# Kasli-SOC_bank500-501.net
KiCad netlist of a schematic drawn in Altium Designer
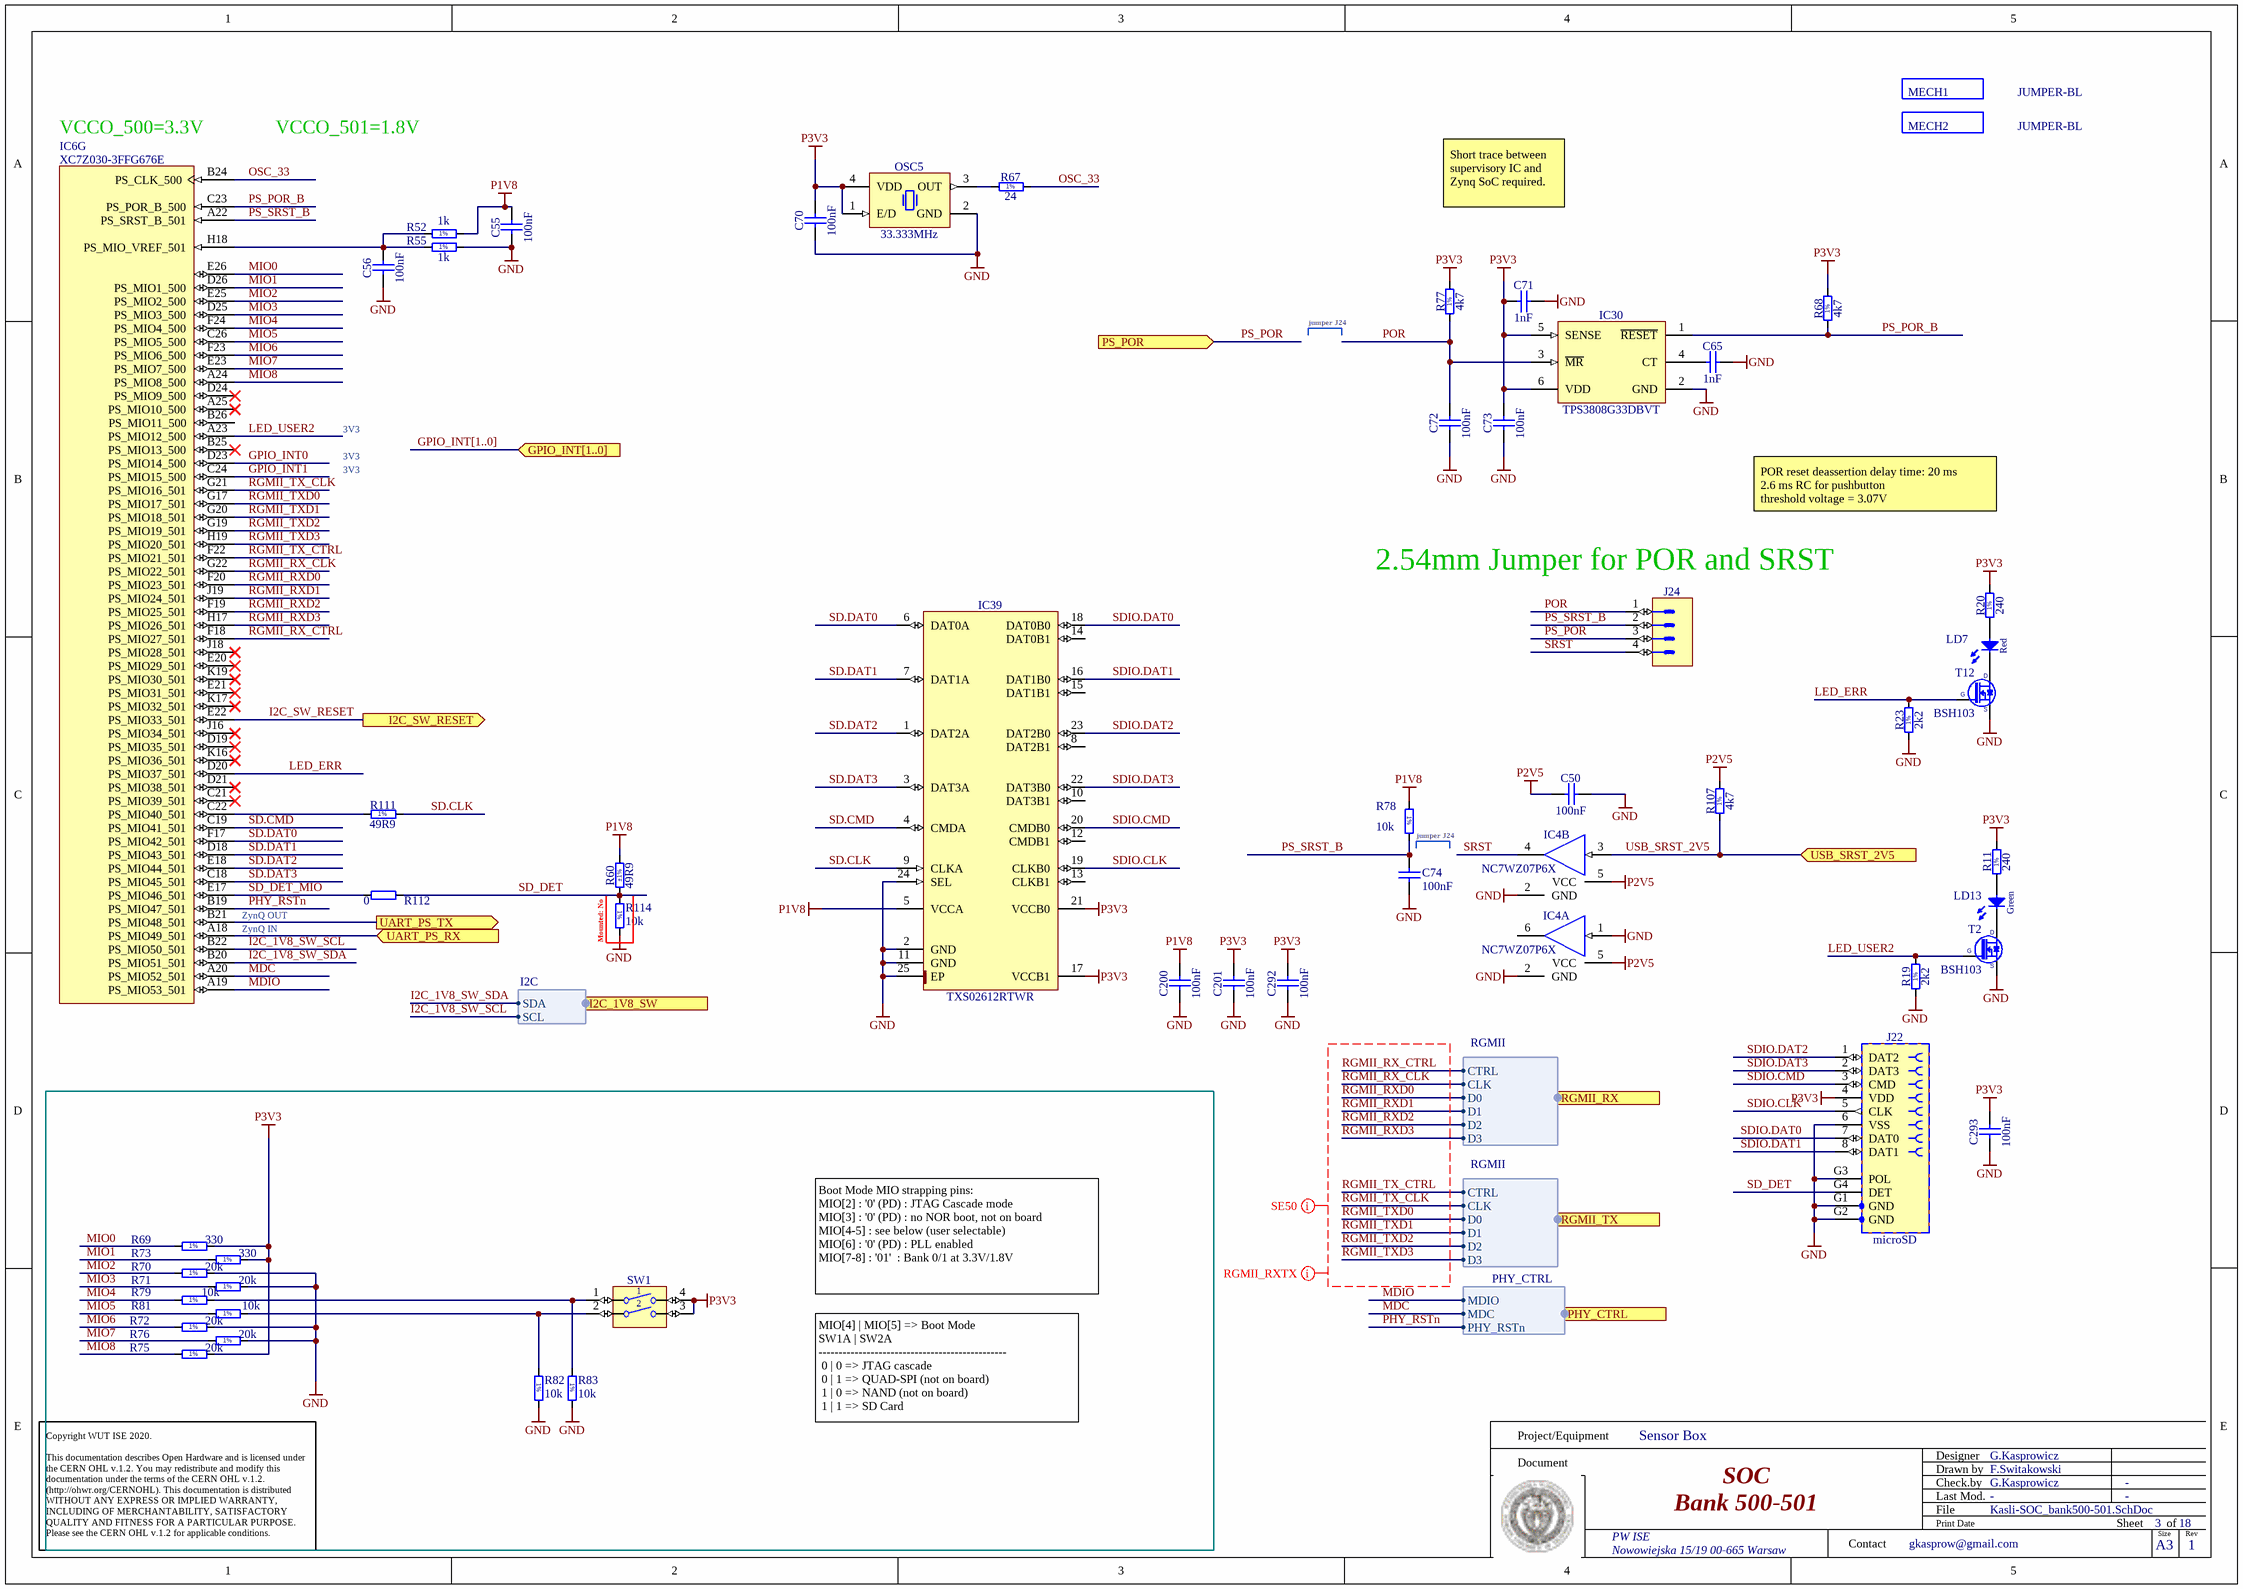
[diagram p0: Kasli-SOC_bank500-501.SchDoc]

(export (version "E")
  (design (tool "Eeschema 10.0.6"))
  (components
    (comp (ref "C50")
      (value "100nF")
      (footprint "CAPC0603X33N")
      (description "Non-polarised capacitor")
      (fields
        (field (name "PART NUMBER") "CC0201_100NF_6.3V_10%_X5R")
        (field (name "VOLTAGE") "6.3V")
        (field (name "AUTHOR") "CERN DEM JLC")
      )
      (libsource (lib "Capacitors") (part "Capacitor - non polarized"))
    )
    (comp (ref "C55")
      (value "100nF")
      (footprint "CAPC1005X55N")
      (description "Non-polarised capacitor")
      (fields
        (field (name "PART NUMBER") "CC0402_100NF_16V_10%_X7R")
        (field (name "VOLTAGE") "16V")
        (field (name "AUTHOR") "CERN DEM JLC")
      )
      (libsource (lib "Capacitors") (part "Capacitor - non polarized"))
    )
    (comp (ref "C56")
      (value "100nF")
      (footprint "CAPC1005X55N")
      (description "Non-polarised capacitor")
      (fields
        (field (name "PART NUMBER") "CC0402_100NF_16V_10%_X7R")
        (field (name "VOLTAGE") "16V")
        (field (name "AUTHOR") "CERN DEM JLC")
      )
      (libsource (lib "Capacitors") (part "Capacitor - non polarized"))
    )
    (comp (ref "C65")
      (value "1nF")
      (footprint "CAPC1005X55N")
      (description "Non-polarised capacitor")
      (fields
        (field (name "PART NUMBER") "CC0402_1NF_50V_10%_X7R")
        (field (name "VOLTAGE") "50V")
        (field (name "AUTHOR") "CERN DEM JLC")
      )
      (libsource (lib "Capacitors") (part "Capacitor - non polarized"))
    )
    (comp (ref "C70")
      (value "100nF")
      (footprint "CAPC1005X55N")
      (description "Non-polarised capacitor")
      (fields
        (field (name "PART NUMBER") "CC0402_100NF_16V_10%_X7R")
        (field (name "VOLTAGE") "16V")
        (field (name "AUTHOR") "CERN DEM JLC")
      )
      (libsource (lib "Capacitors") (part "Capacitor - non polarized"))
    )
    (comp (ref "C71")
      (value "1nF")
      (footprint "CAPC1005X55N")
      (description "Non-polarised capacitor")
      (fields
        (field (name "PART NUMBER") "CC0402_1NF_50V_10%_X7R")
        (field (name "VOLTAGE") "50V")
        (field (name "AUTHOR") "CERN DEM JLC")
      )
      (libsource (lib "Capacitors") (part "Capacitor - non polarized"))
    )
    (comp (ref "C72")
      (value "100nF")
      (footprint "CAPC1005X55N")
      (description "Non-polarised capacitor")
      (fields
        (field (name "PART NUMBER") "CC0402_100NF_16V_10%_X7R")
        (field (name "VOLTAGE") "16V")
        (field (name "AUTHOR") "CERN DEM JLC")
      )
      (libsource (lib "Capacitors") (part "Capacitor - non polarized"))
    )
    (comp (ref "C73")
      (value "100nF")
      (footprint "CAPC1005X55N")
      (description "Non-polarised capacitor")
      (fields
        (field (name "PART NUMBER") "CC0402_100NF_16V_10%_X7R")
        (field (name "VOLTAGE") "16V")
        (field (name "AUTHOR") "CERN DEM JLC")
      )
      (libsource (lib "Capacitors") (part "Capacitor - non polarized"))
    )
    (comp (ref "C74")
      (value "100nF")
      (footprint "CAPC1005X55N")
      (description "Non-polarised capacitor")
      (fields
        (field (name "PART NUMBER") "CC0402_100NF_16V_10%_X7R")
        (field (name "VOLTAGE") "16V")
        (field (name "AUTHOR") "CERN DEM JLC")
      )
      (libsource (lib "Capacitors") (part "Capacitor - non polarized"))
    )
    (comp (ref "C200")
      (value "100nF")
      (footprint "CAPC1005X55N")
      (description "Non-polarised capacitor")
      (fields
        (field (name "PART NUMBER") "CC0402_100NF_16V_10%_X7R")
        (field (name "VOLTAGE") "16V")
        (field (name "AUTHOR") "CERN DEM JLC")
      )
      (libsource (lib "Capacitors") (part "Capacitor - non polarized"))
    )
    (comp (ref "C201")
      (value "100nF")
      (footprint "CAPC1005X55N")
      (description "Non-polarised capacitor")
      (fields
        (field (name "PART NUMBER") "CC0402_100NF_16V_10%_X7R")
        (field (name "VOLTAGE") "16V")
        (field (name "AUTHOR") "CERN DEM JLC")
      )
      (libsource (lib "Capacitors") (part "Capacitor - non polarized"))
    )
    (comp (ref "C292")
      (value "100nF")
      (footprint "CAPC1005X55N")
      (description "Non-polarised capacitor")
      (fields
        (field (name "PART NUMBER") "CC0402_100NF_16V_10%_X7R")
        (field (name "VOLTAGE") "16V")
        (field (name "AUTHOR") "CERN DEM JLC")
      )
      (libsource (lib "Capacitors") (part "Capacitor - non polarized"))
    )
    (comp (ref "C293")
      (value "100nF")
      (footprint "CAPC1005X55N")
      (description "Non-polarised capacitor")
      (fields
        (field (name "PART NUMBER") "CC0402_100NF_16V_10%_X7R")
        (field (name "VOLTAGE") "16V")
        (field (name "AUTHOR") "CERN DEM JLC")
      )
      (libsource (lib "Capacitors") (part "Capacitor - non polarized"))
    )
    (comp (ref "IC4")
      (value "NC7WZ07P6X")
      (footprint "SOT65P210X110-6N")
      (description "TinyLogic® UHS Dual Buffer (Open Drain Outputs)")
      (fields (field (name "MANUFACTURER") "FAIRCHILD SEMICONDUCTOR") (field (name "AUTHOR") "CERN DEM JLC"))
      (libsource (lib "ICs And Semiconductors") (part "NC7W07"))
    )
    (comp (ref "IC6")
      (value "XC7Z030-3FFG676E")
      (footprint "BGA676C100P26X26_2700X2700X324")
      (fields (field (name "MANUFACTURER") "XILINX") (field (name "AUTHOR") "CERN DEM JLC"))
      (libsource (lib "ICs And Semiconductors") (part "XC7Z030-2FFG676I"))
    )
    (comp (ref "IC30")
      (value "TPS3808G33DBVT")
      (footprint "SOT95P280X145-6N")
      (description "Low Quiescent Current, Programmable-Delay Supervisory Circuit")
      (fields (field (name "MANUFACTURER") "TEXAS INSTRUMENTS") (field (name "AUTHOR") "CERN DEM JLC"))
      (libsource (lib "ICs And Semiconductors") (part "TPS3808xxxDBV"))
    )
    (comp (ref "IC39")
      (value "TXS02612RTWR")
      (footprint "QFN50P400X400X80-25N-S255")
      (description "SDIO Port Expander With Voltage-Level Translation")
      (fields (field (name "MANUFACTURER") "TEXAS INSTRUMENTS") (field (name "AUTHOR") "CERN DEM JLC"))
      (libsource (lib "ICs And Semiconductors") (part "TXS02612RTWR"))
    )
    (comp (ref "J22")
      (value "microSD")
      (footprint "MOLEX_47309-2651")
      (description "MicroSD Card Header with Detect Switch")
      (fields
        (field (name "PART NUMBER") "MOLEX_47309-2651")
        (field (name "MANUFACTURER") "MOLEX")
        (field (name "AUTHOR") "CERN DEM JMW")
      )
      (libsource (lib "Connectors") (part "MOLEX_47309-2651"))
    )
    (comp (ref "J24")
      (value "Header 2")
      (footprint "SAMTEC_TSM-102-01-L-DV")
      (description "Connector 4 Male")
      (fields
        (field (name "PART NUMBER") "SAMTEC_TSM-102-01-L-DV")
        (field (name "MANUFACTURER") "SAMTEC")
        (field (name "AUTHOR") "CERN DEM MR")
      )
      (libsource (lib "Connectors") (part "Connector 4 Male"))
    )
    (comp (ref "LD7")
      (value "Red")
      (footprint "LED_AVAGO_HSMC-C120")
      (description "LED Red 1C 2A")
      (fields
        (field (name "MANUFACTURER PART NUMBER") "HSMC-C120")
        (field (name "PART NUMBER") "LED_AVAGO_HSMC-C120")
        (field (name "AUTHOR") "CERN DEM JMW")
      )
      (libsource (lib "ICs And Semiconductors") (part "LED Red 1C 2A"))
    )
    (comp (ref "LD13")
      (value "Green")
      (footprint "LED_AVAGO_HSME-C120")
      (description "LED Green 1C 2A")
      (fields
        (field (name "MANUFACTURER PART NUMBER") "HSME-C120")
        (field (name "PART NUMBER") "LED_AVAGO_HSME-C120")
        (field (name "AUTHOR") "CERN DEM JMW")
      )
      (libsource (lib "ICs And Semiconductors") (part "LED Green 1C 2A"))
    )
    (comp (ref "MECH1")
      (value "JUMPER-BL")
      (description "Jumper")
      (fields (field (name "MANUFACTURER") "NINGI") (field (name "AUTHOR") "GK"))
      (libsource (lib "Mechanical") (part "Generic_mechanical"))
    )
    (comp (ref "MECH2")
      (value "JUMPER-BL")
      (description "Jumper")
      (fields (field (name "MANUFACTURER") "NINGI") (field (name "AUTHOR") "GK"))
      (libsource (lib "Mechanical") (part "Generic_mechanical"))
    )
    (comp (ref "OSC5")
      (value "33.333MHz")
      (footprint "OSC_IDT_XLH7")
      (description "Oscillator 4 pins 1=E/D 2=GND 3=OUT 4=VDD")
      (fields
        (field (name "PART NUMBER") "OSC_33.333MHZ_IDT_XLH736033.333000I")
        (field (name "MANUFACTURER") "IDT")
        (field (name "AUTHOR") "CERN DEM JLC")
      )
      (libsource (lib "ICs And Semiconductors") (part "Oscillator 1E/D 2GND 3OUT 4VDD"))
    )
    (comp (ref "R11")
      (value "240")
      (footprint "RESC1005X40N")
      (description "Resistor - 1%")
      (fields
        (field (name "PART NUMBER") "R0402_240R_1%_0.0625W_100PPM")
        (field (name "POWER") "0.0625W")
        (field (name "AUTHOR") "CERN DEM JLC")
      )
      (libsource (lib "Resistors") (part "Resistor - 1%"))
    )
    (comp (ref "R19")
      (value "2k2")
      (footprint "RESC1005X40N")
      (description "Resistor - 1%")
      (fields
        (field (name "PART NUMBER") "R0402_2K2_1%_0.0625W_100PPM")
        (field (name "POWER") "0.0625W")
        (field (name "AUTHOR") "CERN DEM JLC")
      )
      (libsource (lib "Resistors") (part "Resistor - 1%"))
    )
    (comp (ref "R20")
      (value "240")
      (footprint "RESC1005X40N")
      (description "Resistor - 1%")
      (fields
        (field (name "PART NUMBER") "R0402_240R_1%_0.0625W_100PPM")
        (field (name "POWER") "0.0625W")
        (field (name "AUTHOR") "CERN DEM JLC")
      )
      (libsource (lib "Resistors") (part "Resistor - 1%"))
    )
    (comp (ref "R23")
      (value "2k2")
      (footprint "RESC1005X40N")
      (description "Resistor - 1%")
      (fields
        (field (name "PART NUMBER") "R0402_2K2_1%_0.0625W_100PPM")
        (field (name "POWER") "0.0625W")
        (field (name "AUTHOR") "CERN DEM JLC")
      )
      (libsource (lib "Resistors") (part "Resistor - 1%"))
    )
    (comp (ref "R52")
      (value "1k")
      (footprint "RESC1005X40N")
      (description "Resistor - 1%")
      (fields
        (field (name "PART NUMBER") "R0402_1K_1%_0.0625W_100PPM")
        (field (name "POWER") "0.0625W")
        (field (name "AUTHOR") "CERN DEM JLC")
      )
      (libsource (lib "Resistors") (part "Resistor - 1%"))
    )
    (comp (ref "R55")
      (value "1k")
      (footprint "RESC1005X40N")
      (description "Resistor - 1%")
      (fields
        (field (name "PART NUMBER") "R0402_1K_1%_0.0625W_100PPM")
        (field (name "POWER") "0.0625W")
        (field (name "AUTHOR") "CERN DEM JLC")
      )
      (libsource (lib "Resistors") (part "Resistor - 1%"))
    )
    (comp (ref "R60")
      (value "49R9")
      (footprint "RESC1608X55N")
      (description "Resistor - 1%")
      (fields
        (field (name "TOLERANCE") "±1%")
        (field (name "PART NUMBER") "R0603_49K9_1%_0.1W_100PPM")
        (field (name "POWER") "0.1W")
        (field (name "AUTHOR") "CERN DEM JLC")
      )
      (libsource (lib "") (part "Resistor - 1%_1"))
    )
    (comp (ref "R67")
      (value "24")
      (footprint "RESC1005X40N")
      (description "Resistor - 1%")
      (fields
        (field (name "PART NUMBER") "R0402_24R_1%_0.0625W_100PPM")
        (field (name "POWER") "0.0625W")
        (field (name "AUTHOR") "CERN DEM JLC")
      )
      (libsource (lib "Resistors") (part "Resistor - 1%"))
    )
    (comp (ref "R68")
      (value "4k7")
      (footprint "RESC1005X40N")
      (description "Resistor - 1%")
      (fields
        (field (name "PART NUMBER") "R0402_4K7_1%_0.0625W_100PPM")
        (field (name "POWER") "0.0625W")
        (field (name "AUTHOR") "CERN DEM JLC")
      )
      (libsource (lib "Resistors") (part "Resistor - 1%"))
    )
    (comp (ref "R69")
      (value "330")
      (footprint "RESC1005X40N")
      (description "Resistor - 1%")
      (fields
        (field (name "PART NUMBER") "R0402_330R_1%_0.0625W_100PPM")
        (field (name "POWER") "0.0625W")
        (field (name "AUTHOR") "CERN DEM JLC")
      )
      (libsource (lib "Resistors") (part "Resistor - 1%"))
    )
    (comp (ref "R70")
      (value "20k")
      (footprint "RESC1005X40N")
      (description "Resistor - 1%")
      (fields
        (field (name "PART NUMBER") "R0402_20K_1%_0.0625W_100PPM")
        (field (name "POWER") "0.0625W")
        (field (name "AUTHOR") "CERN DEM JLC")
      )
      (libsource (lib "Resistors") (part "Resistor - 1%"))
    )
    (comp (ref "R71")
      (value "20k")
      (footprint "RESC1005X40N")
      (description "Resistor - 1%")
      (fields
        (field (name "PART NUMBER") "R0402_20K_1%_0.0625W_100PPM")
        (field (name "POWER") "0.0625W")
        (field (name "AUTHOR") "CERN DEM JLC")
      )
      (libsource (lib "Resistors") (part "Resistor - 1%"))
    )
    (comp (ref "R72")
      (value "20k")
      (footprint "RESC1005X40N")
      (description "Resistor - 1%")
      (fields
        (field (name "PART NUMBER") "R0402_20K_1%_0.0625W_100PPM")
        (field (name "POWER") "0.0625W")
        (field (name "AUTHOR") "CERN DEM JLC")
      )
      (libsource (lib "Resistors") (part "Resistor - 1%"))
    )
    (comp (ref "R73")
      (value "330")
      (footprint "RESC1005X40N")
      (description "Resistor - 1%")
      (fields
        (field (name "PART NUMBER") "R0402_330R_1%_0.0625W_100PPM")
        (field (name "POWER") "0.0625W")
        (field (name "AUTHOR") "CERN DEM JLC")
      )
      (libsource (lib "Resistors") (part "Resistor - 1%"))
    )
    (comp (ref "R75")
      (value "20k")
      (footprint "RESC1005X40N")
      (description "Resistor - 1%")
      (fields
        (field (name "PART NUMBER") "R0402_20K_1%_0.0625W_100PPM")
        (field (name "POWER") "0.0625W")
        (field (name "AUTHOR") "CERN DEM JLC")
      )
      (libsource (lib "Resistors") (part "Resistor - 1%"))
    )
    (comp (ref "R76")
      (value "20k")
      (footprint "RESC1005X40N")
      (description "Resistor - 1%")
      (fields
        (field (name "PART NUMBER") "R0402_20K_1%_0.0625W_100PPM")
        (field (name "POWER") "0.0625W")
        (field (name "AUTHOR") "CERN DEM JLC")
      )
      (libsource (lib "Resistors") (part "Resistor - 1%"))
    )
    (comp (ref "R77")
      (value "4k7")
      (footprint "RESC1005X40N")
      (description "Resistor - 1%")
      (fields
        (field (name "PART NUMBER") "R0402_4K7_1%_0.0625W_100PPM")
        (field (name "POWER") "0.0625W")
        (field (name "AUTHOR") "CERN DEM JLC")
      )
      (libsource (lib "Resistors") (part "Resistor - 1%"))
    )
    (comp (ref "R78")
      (value "10k")
      (footprint "RESC1005X40N")
      (description "Resistor - 1%")
      (fields
        (field (name "PART NUMBER") "R0402_10K_1%_0.0625W_100PPM")
        (field (name "POWER") "0.0625W")
        (field (name "AUTHOR") "CERN DEM JLC")
      )
      (libsource (lib "Resistors") (part "Resistor - 1%"))
    )
    (comp (ref "R79")
      (value "10k")
      (footprint "RESC1005X40N")
      (description "Resistor - 1%")
      (fields
        (field (name "PART NUMBER") "R0402_10K_1%_0.0625W_100PPM")
        (field (name "POWER") "0.0625W")
        (field (name "AUTHOR") "CERN DEM JLC")
      )
      (libsource (lib "Resistors") (part "Resistor - 1%"))
    )
    (comp (ref "R81")
      (value "10k")
      (footprint "RESC1005X40N")
      (description "Resistor - 1%")
      (fields
        (field (name "PART NUMBER") "R0402_10K_1%_0.0625W_100PPM")
        (field (name "POWER") "0.0625W")
        (field (name "AUTHOR") "CERN DEM JLC")
      )
      (libsource (lib "Resistors") (part "Resistor - 1%"))
    )
    (comp (ref "R82")
      (value "10k")
      (footprint "RESC1005X40N")
      (description "Resistor - 1%")
      (fields
        (field (name "PART NUMBER") "R0402_10K_1%_0.0625W_100PPM")
        (field (name "POWER") "0.0625W")
        (field (name "AUTHOR") "CERN DEM JLC")
      )
      (libsource (lib "Resistors") (part "Resistor - 1%"))
    )
    (comp (ref "R83")
      (value "10k")
      (footprint "RESC1005X40N")
      (description "Resistor - 1%")
      (fields
        (field (name "PART NUMBER") "R0402_10K_1%_0.0625W_100PPM")
        (field (name "POWER") "0.0625W")
        (field (name "AUTHOR") "CERN DEM JLC")
      )
      (libsource (lib "Resistors") (part "Resistor - 1%"))
    )
    (comp (ref "R107")
      (value "4k7")
      (footprint "RESC1005X40N")
      (description "Resistor - 1%")
      (fields
        (field (name "PART NUMBER") "R0402_4K7_1%_0.0625W_100PPM")
        (field (name "POWER") "0.0625W")
        (field (name "AUTHOR") "CERN DEM JLC")
      )
      (libsource (lib "Resistors") (part "Resistor - 1%"))
    )
    (comp (ref "R111")
      (value "49R9")
      (footprint "RESC1005X40N")
      (description "Resistor - 1%")
      (fields
        (field (name "PART NUMBER") "R0402_49R9_1%_0.0625W_100PPM")
        (field (name "POWER") "0.0625W")
        (field (name "AUTHOR") "CERN DEM JLC")
      )
      (libsource (lib "Resistors") (part "Resistor - 1%"))
    )
    (comp (ref "R112")
      (value "0")
      (footprint "RESC1005X40N")
      (description "Resistor")
      (fields
        (field (name "PART NUMBER") "R0402_0R_JUMPER")
        (field (name "MANUFACTURER") "GENERIC")
        (field (name "AUTHOR") "CERN DEM JLC")
      )
      (libsource (lib "Resistors") (part "Resistor"))
    )
    (comp (ref "R114")
      (value "10k")
      (footprint "RESC1005X40N")
      (description "Resistor - 1%")
      (fields
        (field (name "PART NUMBER") "R0402_10K_1%_0.0625W_100PPM")
        (field (name "POWER") "0.0625W")
        (field (name "AUTHOR") "CERN DEM JLC")
      )
      (libsource (lib "Resistors") (part "Resistor - 1%"))
    )
    (comp (ref "SW1")
      (value "Switch")
      (footprint "SW_TYCO_1571983-1")
      (description "2 Ways SPST DIP Switch")
      (fields
        (field (name "PART NUMBER") "SW_TYCO_1571983-1")
        (field (name "MANUFACTURER") "TYCO")
        (field (name "AUTHOR") "CERN DEM JLC")
      )
      (libsource (lib "Eletro-mechanical") (part "SW 2x SPST DIP Switch"))
    )
    (comp (ref "T2")
      (value "BSH103")
      (footprint "SOT95P230X110-3N")
      (description "N-CHANNEL MOSFET WITH DIODE")
      (fields (field (name "MANUFACTURER") "NEXPERIA") (field (name "AUTHOR") "CERN DEM JLC"))
      (libsource (lib "ICs And Semiconductors") (part "N-MOSFET-D 1G 2S 3D"))
    )
    (comp (ref "T12")
      (value "BSH103")
      (footprint "SOT95P230X110-3N")
      (description "N-CHANNEL MOSFET WITH DIODE")
      (fields (field (name "MANUFACTURER") "NEXPERIA") (field (name "AUTHOR") "CERN DEM JLC"))
      (libsource (lib "ICs And Semiconductors") (part "N-MOSFET-D 1G 2S 3D"))
    )
  )
  (nets
    (net (code "4") (name "/GPIO_INT0") (class "Default")
      (node (ref "IC6") (pin "D23") (pinfunction "PS_MIO14_500_D23") (pintype "bidirectional"))
    )
    (net (code "5") (name "/GPIO_INT1") (class "Default")
      (node (ref "IC6") (pin "C24") (pinfunction "PS_MIO15_500_C24") (pintype "bidirectional"))
    )
    (net (code "7") (name "/I2C_1V8_SW_SCL") (class "Default")
      (node (ref "IC6") (pin "B22") (pinfunction "PS_MIO50_501_B22") (pintype "bidirectional"))
    )
    (net (code "8") (name "/I2C_1V8_SW_SDA") (class "Default")
      (node (ref "IC6") (pin "B20") (pinfunction "PS_MIO51_501_B20") (pintype "bidirectional"))
    )
    (net (code "9") (name "/I2C_SW_RESET") (class "Default")
      (node (ref "IC6") (pin "E22") (pinfunction "PS_MIO33_501_E22") (pintype "bidirectional"))
    )
    (net (code "10") (name "/LED_ERR") (class "Default")
      (node (ref "IC6") (pin "D20") (pinfunction "PS_MIO37_501_D20") (pintype "bidirectional"))
      (node (ref "R23") (pin "2") (pinfunction "2_2") (pintype "passive"))
      (node (ref "T12") (pin "1") (pinfunction "G_1") (pintype "passive"))
    )
    (net (code "11") (name "/LED_USER2") (class "Default")
      (node (ref "IC6") (pin "A23") (pinfunction "PS_MIO12_500_A23") (pintype "bidirectional"))
      (node (ref "R19") (pin "2") (pinfunction "2_2") (pintype "passive"))
      (node (ref "T2") (pin "1") (pinfunction "G_1") (pintype "passive"))
    )
    (net (code "12") (name "/MDC") (class "Default")
      (node (ref "IC6") (pin "A20") (pinfunction "PS_MIO52_501_A20") (pintype "bidirectional"))
    )
    (net (code "13") (name "/MDIO") (class "Default")
      (node (ref "IC6") (pin "A19") (pinfunction "PS_MIO53_501_A19") (pintype "bidirectional"))
    )
    (net (code "14") (name "/MIO0") (class "Default")
      (node (ref "IC6") (pin "E26") (pinfunction "PS_MIO0_500_E26") (pintype "bidirectional"))
      (node (ref "R69") (pin "1") (pinfunction "1_1") (pintype "passive"))
    )
    (net (code "15") (name "/MIO1") (class "Default")
      (node (ref "IC6") (pin "D26") (pinfunction "PS_MIO1_500_D26") (pintype "bidirectional"))
      (node (ref "R73") (pin "1") (pinfunction "1_1") (pintype "passive"))
    )
    (net (code "16") (name "/MIO2") (class "Default")
      (node (ref "IC6") (pin "E25") (pinfunction "PS_MIO2_500_E25") (pintype "bidirectional"))
      (node (ref "R70") (pin "1") (pinfunction "1_1") (pintype "passive"))
    )
    (net (code "17") (name "/MIO3") (class "Default")
      (node (ref "IC6") (pin "D25") (pinfunction "PS_MIO3_500_D25") (pintype "bidirectional"))
      (node (ref "R71") (pin "1") (pinfunction "1_1") (pintype "passive"))
    )
    (net (code "18") (name "/MIO4") (class "Default")
      (node (ref "IC6") (pin "F24") (pinfunction "PS_MIO4_500_F24") (pintype "bidirectional"))
      (node (ref "R79") (pin "1") (pinfunction "1_1") (pintype "passive"))
    )
    (net (code "19") (name "/MIO5") (class "Default")
      (node (ref "IC6") (pin "C26") (pinfunction "PS_MIO5_500_C26") (pintype "bidirectional"))
      (node (ref "R81") (pin "1") (pinfunction "1_1") (pintype "passive"))
    )
    (net (code "20") (name "/MIO6") (class "Default")
      (node (ref "IC6") (pin "F23") (pinfunction "PS_MIO6_500_F23") (pintype "bidirectional"))
      (node (ref "R72") (pin "1") (pinfunction "1_1") (pintype "passive"))
    )
    (net (code "21") (name "/MIO7") (class "Default")
      (node (ref "IC6") (pin "E23") (pinfunction "PS_MIO7_500_E23") (pintype "bidirectional"))
      (node (ref "R76") (pin "1") (pinfunction "1_1") (pintype "passive"))
    )
    (net (code "22") (name "/MIO8") (class "Default")
      (node (ref "IC6") (pin "A24") (pinfunction "PS_MIO8_500_A24") (pintype "bidirectional"))
      (node (ref "R75") (pin "1") (pinfunction "1_1") (pintype "passive"))
    )
    (net (code "23") (name "/OSC_33") (class "Default")
      (node (ref "IC6") (pin "B24") (pinfunction "PS_CLK_500_B24") (pintype "input"))
      (node (ref "R67") (pin "2") (pinfunction "2_2") (pintype "passive"))
    )
    (net (code "24") (name "/PHY_RSTn") (class "Default")
      (node (ref "IC6") (pin "B19") (pinfunction "PS_MIO47_501_B19") (pintype "bidirectional"))
    )
    (net (code "25") (name "/POR") (class "Default")
      (node (ref "C72") (pin "2") (pinfunction "2_2") (pintype "passive"))
      (node (ref "IC30") (pin "3") (pinfunction "~{MR}_3") (pintype "input"))
      (node (ref "J24") (pin "1") (pinfunction "1_1") (pintype "bidirectional"))
      (node (ref "R77") (pin "1") (pinfunction "1_1") (pintype "passive"))
    )
    (net (code "26") (name "/PS_POR") (class "Default")
      (node (ref "J24") (pin "3") (pinfunction "3_3") (pintype "bidirectional"))
    )
    (net (code "27") (name "/PS_POR_B") (class "Default")
      (node (ref "IC30") (pin "1") (pinfunction "~{RESET}_1") (pintype "open_collector"))
      (node (ref "IC6") (pin "C23") (pinfunction "PS_POR_B_500_C23") (pintype "input"))
      (node (ref "R68") (pin "1") (pinfunction "1_1") (pintype "passive"))
    )
    (net (code "28") (name "/PS_SRST_B") (class "Default")
      (node (ref "C74") (pin "1") (pinfunction "1_1") (pintype "passive"))
      (node (ref "IC6") (pin "A22") (pinfunction "PS_SRST_B_501_A22") (pintype "input"))
      (node (ref "J24") (pin "2") (pinfunction "2_2") (pintype "bidirectional"))
      (node (ref "R78") (pin "2") (pinfunction "2_2") (pintype "passive"))
    )
    (net (code "29") (name "/RGMII_RXD0") (class "Default")
      (node (ref "IC6") (pin "F20") (pinfunction "PS_MIO23_501_F20") (pintype "bidirectional"))
    )
    (net (code "30") (name "/RGMII_RXD1") (class "Default")
      (node (ref "IC6") (pin "J19") (pinfunction "PS_MIO24_501_J19") (pintype "bidirectional"))
    )
    (net (code "31") (name "/RGMII_RXD2") (class "Default")
      (node (ref "IC6") (pin "F19") (pinfunction "PS_MIO25_501_F19") (pintype "bidirectional"))
    )
    (net (code "32") (name "/RGMII_RXD3") (class "Default")
      (node (ref "IC6") (pin "H17") (pinfunction "PS_MIO26_501_H17") (pintype "bidirectional"))
    )
    (net (code "33") (name "/RGMII_RX_CLK") (class "Default")
      (node (ref "IC6") (pin "G22") (pinfunction "PS_MIO22_501_G22") (pintype "bidirectional"))
    )
    (net (code "34") (name "/RGMII_RX_CTRL") (class "Default")
      (node (ref "IC6") (pin "F18") (pinfunction "PS_MIO27_501_F18") (pintype "bidirectional"))
    )
    (net (code "35") (name "/RGMII_TXD0") (class "Default")
      (node (ref "IC6") (pin "G17") (pinfunction "PS_MIO17_501_G17") (pintype "bidirectional"))
    )
    (net (code "36") (name "/RGMII_TXD1") (class "Default")
      (node (ref "IC6") (pin "G20") (pinfunction "PS_MIO18_501_G20") (pintype "bidirectional"))
    )
    (net (code "37") (name "/RGMII_TXD2") (class "Default")
      (node (ref "IC6") (pin "G19") (pinfunction "PS_MIO19_501_G19") (pintype "bidirectional"))
    )
    (net (code "38") (name "/RGMII_TXD3") (class "Default")
      (node (ref "IC6") (pin "H19") (pinfunction "PS_MIO20_501_H19") (pintype "bidirectional"))
    )
    (net (code "39") (name "/RGMII_TX_CLK") (class "Default")
      (node (ref "IC6") (pin "G21") (pinfunction "PS_MIO16_501_G21") (pintype "bidirectional"))
    )
    (net (code "40") (name "/RGMII_TX_CTRL") (class "Default")
      (node (ref "IC6") (pin "F22") (pinfunction "PS_MIO21_501_F22") (pintype "bidirectional"))
    )
    (net (code "41") (name "/SD.CLK") (class "Default")
      (node (ref "IC39") (pin "9") (pinfunction "CLKA_9") (pintype "input"))
      (node (ref "R111") (pin "2") (pinfunction "2_2") (pintype "passive"))
    )
    (net (code "42") (name "/SD.CMD") (class "Default")
      (node (ref "IC39") (pin "4") (pinfunction "CMDA_4") (pintype "bidirectional"))
      (node (ref "IC6") (pin "C19") (pinfunction "PS_MIO41_501_C19") (pintype "bidirectional"))
    )
    (net (code "43") (name "/SD.DAT0") (class "Default")
      (node (ref "IC39") (pin "6") (pinfunction "DAT0A_6") (pintype "bidirectional"))
      (node (ref "IC6") (pin "F17") (pinfunction "PS_MIO42_501_F17") (pintype "bidirectional"))
    )
    (net (code "44") (name "/SD.DAT1") (class "Default")
      (node (ref "IC39") (pin "7") (pinfunction "DAT1A_7") (pintype "bidirectional"))
      (node (ref "IC6") (pin "D18") (pinfunction "PS_MIO43_501_D18") (pintype "bidirectional"))
    )
    (net (code "45") (name "/SD.DAT2") (class "Default")
      (node (ref "IC39") (pin "1") (pinfunction "DAT2A_1") (pintype "bidirectional"))
      (node (ref "IC6") (pin "E18") (pinfunction "PS_MIO44_501_E18") (pintype "bidirectional"))
    )
    (net (code "46") (name "/SD.DAT3") (class "Default")
      (node (ref "IC39") (pin "3") (pinfunction "DAT3A_3") (pintype "bidirectional"))
      (node (ref "IC6") (pin "C18") (pinfunction "PS_MIO45_501_C18") (pintype "bidirectional"))
    )
    (net (code "47") (name "/SDIO.CLK") (class "Default")
      (node (ref "IC39") (pin "19") (pinfunction "CLKB0_19") (pintype "bidirectional"))
      (node (ref "J22") (pin "5") (pinfunction "CLK_5") (pintype "output"))
    )
    (net (code "48") (name "/SDIO.CMD") (class "Default")
      (node (ref "IC39") (pin "20") (pinfunction "CMDB0_20") (pintype "bidirectional"))
      (node (ref "J22") (pin "3") (pinfunction "CMD_3") (pintype "bidirectional"))
    )
    (net (code "49") (name "/SDIO.DAT0") (class "Default")
      (node (ref "IC39") (pin "18") (pinfunction "DAT0B0_18") (pintype "bidirectional"))
      (node (ref "J22") (pin "7") (pinfunction "DAT0_7") (pintype "bidirectional"))
    )
    (net (code "50") (name "/SDIO.DAT1") (class "Default")
      (node (ref "IC39") (pin "16") (pinfunction "DAT1B0_16") (pintype "bidirectional"))
      (node (ref "J22") (pin "8") (pinfunction "DAT1_8") (pintype "bidirectional"))
    )
    (net (code "51") (name "/SDIO.DAT2") (class "Default")
      (node (ref "IC39") (pin "23") (pinfunction "DAT2B0_23") (pintype "bidirectional"))
      (node (ref "J22") (pin "1") (pinfunction "DAT2_1") (pintype "bidirectional"))
    )
    (net (code "52") (name "/SDIO.DAT3") (class "Default")
      (node (ref "IC39") (pin "22") (pinfunction "DAT3B0_22") (pintype "bidirectional"))
      (node (ref "J22") (pin "2") (pinfunction "DAT3_2") (pintype "bidirectional"))
    )
    (net (code "53") (name "/SD_DET") (class "Default")
      (node (ref "J22") (pin "G4") (pinfunction "DET_G4") (pintype "passive"))
      (node (ref "R112") (pin "1") (pinfunction "1_1") (pintype "passive"))
      (node (ref "R114") (pin "1") (pinfunction "1_1") (pintype "passive"))
      (node (ref "R60") (pin "1") (pinfunction "1_1") (pintype "passive"))
    )
    (net (code "54") (name "/SD_DET_MIO") (class "Default")
      (node (ref "IC6") (pin "E17") (pinfunction "PS_MIO46_501_E17") (pintype "bidirectional"))
      (node (ref "R112") (pin "2") (pinfunction "2_2") (pintype "passive"))
    )
    (net (code "55") (name "/SRST") (class "Default")
      (node (ref "IC4") (pin "4") (pinfunction "OUT_4") (pintype "open_collector"))
      (node (ref "J24") (pin "4") (pinfunction "4_4") (pintype "bidirectional"))
    )
    (net (code "56") (name "/UART_PS_RX") (class "Default")
      (node (ref "IC6") (pin "A18") (pinfunction "PS_MIO49_501_A18") (pintype "bidirectional"))
    )
    (net (code "57") (name "/UART_PS_TX") (class "Default")
      (node (ref "IC6") (pin "B21") (pinfunction "PS_MIO48_501_B21") (pintype "bidirectional"))
    )
    (net (code "58") (name "/USB_SRST_2V5") (class "Default")
      (node (ref "IC4") (pin "3") (pinfunction "IN_3") (pintype "input"))
      (node (ref "R107") (pin "1") (pinfunction "1_1") (pintype "passive"))
    )
    (net (code "62") (name "GND") (class "Default")
      (node (ref "C200") (pin "1") (pinfunction "1_1") (pintype "passive"))
      (node (ref "C201") (pin "1") (pinfunction "1_1") (pintype "passive"))
      (node (ref "C292") (pin "1") (pinfunction "1_1") (pintype "passive"))
      (node (ref "C293") (pin "1") (pinfunction "1_1") (pintype "passive"))
      (node (ref "C50") (pin "2") (pinfunction "2_2") (pintype "passive"))
      (node (ref "C55") (pin "1") (pinfunction "1_1") (pintype "passive"))
      (node (ref "C56") (pin "1") (pinfunction "1_1") (pintype "passive"))
      (node (ref "C65") (pin "2") (pinfunction "2_2") (pintype "passive"))
      (node (ref "C70") (pin "1") (pinfunction "1_1") (pintype "passive"))
      (node (ref "C71") (pin "2") (pinfunction "2_2") (pintype "passive"))
      (node (ref "C72") (pin "1") (pinfunction "1_1") (pintype "passive"))
      (node (ref "C73") (pin "1") (pinfunction "1_1") (pintype "passive"))
      (node (ref "C74") (pin "2") (pinfunction "2_2") (pintype "passive"))
      (node (ref "IC30") (pin "2") (pinfunction "GND_2") (pintype "power_in"))
      (node (ref "IC39") (pin "11") (pinfunction "GND_11") (pintype "power_in"))
      (node (ref "IC39") (pin "2") (pinfunction "GND_2") (pintype "power_in"))
      (node (ref "IC39") (pin "24") (pinfunction "SEL_24") (pintype "input"))
      (node (ref "IC39") (pin "25") (pinfunction "EP_25") (pintype "power_in"))
      (node (ref "IC4") (pin "1") (pinfunction "IN_1") (pintype "input"))
      (node (ref "IC4") (pin "2") (pinfunction "GND_2") (pintype "power_in"))
      (node (ref "J22") (pin "6") (pinfunction "VSS_6") (pintype "power_in"))
      (node (ref "J22") (pin "G1") (pinfunction "GND_G1") (pintype "passive"))
      (node (ref "J22") (pin "G2") (pinfunction "GND_G2") (pintype "passive"))
      (node (ref "J22") (pin "G3") (pinfunction "POL_G3") (pintype "passive"))
      (node (ref "OSC5") (pin "2") (pinfunction "GND_2") (pintype "power_in"))
      (node (ref "R114") (pin "2") (pinfunction "2_2") (pintype "passive"))
      (node (ref "R19") (pin "1") (pinfunction "1_1") (pintype "passive"))
      (node (ref "R23") (pin "1") (pinfunction "1_1") (pintype "passive"))
      (node (ref "R55") (pin "2") (pinfunction "2_2") (pintype "passive"))
      (node (ref "R70") (pin "2") (pinfunction "2_2") (pintype "passive"))
      (node (ref "R71") (pin "2") (pinfunction "2_2") (pintype "passive"))
      (node (ref "R72") (pin "2") (pinfunction "2_2") (pintype "passive"))
      (node (ref "R76") (pin "2") (pinfunction "2_2") (pintype "passive"))
      (node (ref "R82") (pin "2") (pinfunction "2_2") (pintype "passive"))
      (node (ref "R83") (pin "2") (pinfunction "2_2") (pintype "passive"))
      (node (ref "T12") (pin "2") (pinfunction "S_2") (pintype "passive"))
      (node (ref "T2") (pin "2") (pinfunction "S_2") (pintype "passive"))
    )
    (net (code "63") (name "Net-(IC6G-PS_MIO40_501)") (class "Default")
      (node (ref "IC6") (pin "C22") (pinfunction "PS_MIO40_501_C22") (pintype "bidirectional"))
      (node (ref "R111") (pin "1") (pinfunction "1_1") (pintype "passive"))
    )
    (net (code "64") (name "Net-(IC6G-PS_MIO_VREF_501)") (class "Default")
      (node (ref "C56") (pin "2") (pinfunction "2_2") (pintype "passive"))
      (node (ref "IC6") (pin "H18") (pinfunction "PS_MIO_VREF_501_H18") (pintype "input"))
      (node (ref "R52") (pin "1") (pinfunction "1_1") (pintype "passive"))
      (node (ref "R55") (pin "1") (pinfunction "1_1") (pintype "passive"))
    )
    (net (code "65") (name "Net-(IC30-CT)") (class "Default")
      (node (ref "C65") (pin "1") (pinfunction "1_1") (pintype "passive"))
      (node (ref "IC30") (pin "4") (pinfunction "CT_4") (pintype "passive"))
    )
    (net (code "66") (name "Net-(LD7-A)") (class "Default")
      (node (ref "LD7") (pin "2") (pinfunction "A_2") (pintype "passive"))
      (node (ref "R20") (pin "1") (pinfunction "1_1") (pintype "passive"))
    )
    (net (code "67") (name "Net-(LD7-C)") (class "Default")
      (node (ref "LD7") (pin "1") (pinfunction "C_1") (pintype "passive"))
      (node (ref "T12") (pin "3") (pinfunction "D_3") (pintype "passive"))
    )
    (net (code "68") (name "Net-(LD13-A)") (class "Default")
      (node (ref "LD13") (pin "2") (pinfunction "A_2") (pintype "passive"))
      (node (ref "R11") (pin "1") (pinfunction "1_1") (pintype "passive"))
    )
    (net (code "69") (name "Net-(LD13-C)") (class "Default")
      (node (ref "LD13") (pin "1") (pinfunction "C_1") (pintype "passive"))
      (node (ref "T2") (pin "3") (pinfunction "D_3") (pintype "passive"))
    )
    (net (code "70") (name "Net-(OSC5-OUT)") (class "Default")
      (node (ref "OSC5") (pin "3") (pinfunction "OUT_3") (pintype "output"))
      (node (ref "R67") (pin "1") (pinfunction "1_1") (pintype "passive"))
    )
    (net (code "71") (name "Net-(R79-Pad2)") (class "Default")
      (node (ref "R79") (pin "2") (pinfunction "2_2") (pintype "passive"))
      (node (ref "R83") (pin "1") (pinfunction "1_1") (pintype "passive"))
      (node (ref "SW1") (pin "1") (pinfunction "1_1") (pintype "bidirectional"))
    )
    (net (code "72") (name "Net-(R81-Pad2)") (class "Default")
      (node (ref "R81") (pin "2") (pinfunction "2_2") (pintype "passive"))
      (node (ref "R82") (pin "1") (pinfunction "1_1") (pintype "passive"))
      (node (ref "SW1") (pin "2") (pinfunction "2_2") (pintype "bidirectional"))
    )
    (net (code "73") (name "P1V8") (class "Default")
      (node (ref "C200") (pin "2") (pinfunction "2_2") (pintype "passive"))
      (node (ref "C55") (pin "2") (pinfunction "2_2") (pintype "passive"))
      (node (ref "IC39") (pin "5") (pinfunction "VCCA_5") (pintype "power_in"))
      (node (ref "R52") (pin "2") (pinfunction "2_2") (pintype "passive"))
      (node (ref "R60") (pin "2") (pinfunction "2_2") (pintype "passive"))
      (node (ref "R78") (pin "1") (pinfunction "1_1") (pintype "passive"))
    )
    (net (code "74") (name "P2V5") (class "Default")
      (node (ref "C50") (pin "1") (pinfunction "1_1") (pintype "passive"))
      (node (ref "IC4") (pin "5") (pinfunction "VCC_5") (pintype "power_in"))
      (node (ref "R107") (pin "2") (pinfunction "2_2") (pintype "passive"))
    )
    (net (code "75") (name "P3V3") (class "Default")
      (node (ref "C201") (pin "2") (pinfunction "2_2") (pintype "passive"))
      (node (ref "C292") (pin "2") (pinfunction "2_2") (pintype "passive"))
      (node (ref "C293") (pin "2") (pinfunction "2_2") (pintype "passive"))
      (node (ref "C70") (pin "2") (pinfunction "2_2") (pintype "passive"))
      (node (ref "C71") (pin "1") (pinfunction "1_1") (pintype "passive"))
      (node (ref "C73") (pin "2") (pinfunction "2_2") (pintype "passive"))
      (node (ref "IC30") (pin "5") (pinfunction "SENSE_5") (pintype "input"))
      (node (ref "IC30") (pin "6") (pinfunction "VDD_6") (pintype "power_in"))
      (node (ref "IC39") (pin "17") (pinfunction "VCCB1_17") (pintype "power_in"))
      (node (ref "IC39") (pin "21") (pinfunction "VCCB0_21") (pintype "power_in"))
      (node (ref "J22") (pin "4") (pinfunction "VDD_4") (pintype "power_in"))
      (node (ref "OSC5") (pin "1") (pinfunction "E/D_1") (pintype "input"))
      (node (ref "OSC5") (pin "4") (pinfunction "VDD_4") (pintype "power_in"))
      (node (ref "R11") (pin "2") (pinfunction "2_2") (pintype "passive"))
      (node (ref "R20") (pin "2") (pinfunction "2_2") (pintype "passive"))
      (node (ref "R68") (pin "2") (pinfunction "2_2") (pintype "passive"))
      (node (ref "R69") (pin "2") (pinfunction "2_2") (pintype "passive"))
      (node (ref "R73") (pin "2") (pinfunction "2_2") (pintype "passive"))
      (node (ref "R75") (pin "2") (pinfunction "2_2") (pintype "passive"))
      (node (ref "R77") (pin "2") (pinfunction "2_2") (pintype "passive"))
      (node (ref "SW1") (pin "3") (pinfunction "3_3") (pintype "bidirectional"))
      (node (ref "SW1") (pin "4") (pinfunction "4_4") (pintype "bidirectional"))
    )
    (net (code "76") (name "unconnected-(IC4A-OUT-Pad6)") (class "Default")
      (node (ref "IC4") (pin "6") (pinfunction "OUT_6") (pintype "open_collector"))
    )
    (net (code "77") (name "unconnected-(IC6G-PS_MIO9_500-PadD24)") (class "Default")
      (node (ref "IC6") (pin "D24") (pinfunction "PS_MIO9_500_D24") (pintype "bidirectional+no_connect"))
    )
    (net (code "78") (name "unconnected-(IC6G-PS_MIO10_500-PadA25)") (class "Default")
      (node (ref "IC6") (pin "A25") (pinfunction "PS_MIO10_500_A25") (pintype "bidirectional+no_connect"))
    )
    (net (code "79") (name "unconnected-(IC6G-PS_MIO11_500-PadB26)") (class "Default")
      (node (ref "IC6") (pin "B26") (pinfunction "PS_MIO11_500_B26") (pintype "bidirectional"))
    )
    (net (code "80") (name "unconnected-(IC6G-PS_MIO13_500-PadB25)") (class "Default")
      (node (ref "IC6") (pin "B25") (pinfunction "PS_MIO13_500_B25") (pintype "bidirectional+no_connect"))
    )
    (net (code "81") (name "unconnected-(IC6G-PS_MIO28_501-PadJ18)") (class "Default")
      (node (ref "IC6") (pin "J18") (pinfunction "PS_MIO28_501_J18") (pintype "bidirectional+no_connect"))
    )
    (net (code "82") (name "unconnected-(IC6G-PS_MIO29_501-PadE20)") (class "Default")
      (node (ref "IC6") (pin "E20") (pinfunction "PS_MIO29_501_E20") (pintype "bidirectional+no_connect"))
    )
    (net (code "83") (name "unconnected-(IC6G-PS_MIO30_501-PadK19)") (class "Default")
      (node (ref "IC6") (pin "K19") (pinfunction "PS_MIO30_501_K19") (pintype "bidirectional+no_connect"))
    )
    (net (code "84") (name "unconnected-(IC6G-PS_MIO31_501-PadE21)") (class "Default")
      (node (ref "IC6") (pin "E21") (pinfunction "PS_MIO31_501_E21") (pintype "bidirectional+no_connect"))
    )
    (net (code "85") (name "unconnected-(IC6G-PS_MIO32_501-PadK17)") (class "Default")
      (node (ref "IC6") (pin "K17") (pinfunction "PS_MIO32_501_K17") (pintype "bidirectional+no_connect"))
    )
    (net (code "86") (name "unconnected-(IC6G-PS_MIO34_501-PadJ16)") (class "Default")
      (node (ref "IC6") (pin "J16") (pinfunction "PS_MIO34_501_J16") (pintype "bidirectional+no_connect"))
    )
    (net (code "87") (name "unconnected-(IC6G-PS_MIO35_501-PadD19)") (class "Default")
      (node (ref "IC6") (pin "D19") (pinfunction "PS_MIO35_501_D19") (pintype "bidirectional+no_connect"))
    )
    (net (code "88") (name "unconnected-(IC6G-PS_MIO36_501-PadK16)") (class "Default")
      (node (ref "IC6") (pin "K16") (pinfunction "PS_MIO36_501_K16") (pintype "bidirectional+no_connect"))
    )
    (net (code "89") (name "unconnected-(IC6G-PS_MIO38_501-PadD21)") (class "Default")
      (node (ref "IC6") (pin "D21") (pinfunction "PS_MIO38_501_D21") (pintype "bidirectional+no_connect"))
    )
    (net (code "90") (name "unconnected-(IC6G-PS_MIO39_501-PadC21)") (class "Default")
      (node (ref "IC6") (pin "C21") (pinfunction "PS_MIO39_501_C21") (pintype "bidirectional+no_connect"))
    )
    (net (code "91") (name "unconnected-(IC39-CLKB1-Pad13)") (class "Default")
      (node (ref "IC39") (pin "13") (pinfunction "CLKB1_13") (pintype "bidirectional"))
    )
    (net (code "92") (name "unconnected-(IC39-CMDB1-Pad12)") (class "Default")
      (node (ref "IC39") (pin "12") (pinfunction "CMDB1_12") (pintype "bidirectional"))
    )
    (net (code "93") (name "unconnected-(IC39-DAT0B1-Pad14)") (class "Default")
      (node (ref "IC39") (pin "14") (pinfunction "DAT0B1_14") (pintype "bidirectional"))
    )
    (net (code "94") (name "unconnected-(IC39-DAT1B1-Pad15)") (class "Default")
      (node (ref "IC39") (pin "15") (pinfunction "DAT1B1_15") (pintype "bidirectional"))
    )
    (net (code "95") (name "unconnected-(IC39-DAT2B1-Pad8)") (class "Default")
      (node (ref "IC39") (pin "8") (pinfunction "DAT2B1_8") (pintype "bidirectional"))
    )
    (net (code "96") (name "unconnected-(IC39-DAT3B1-Pad10)") (class "Default")
      (node (ref "IC39") (pin "10") (pinfunction "DAT3B1_10") (pintype "bidirectional"))
    )
  )
)
